# USB-UART-Wiring-Example.net
KiCad netlist of a schematic drawn in EAGLE
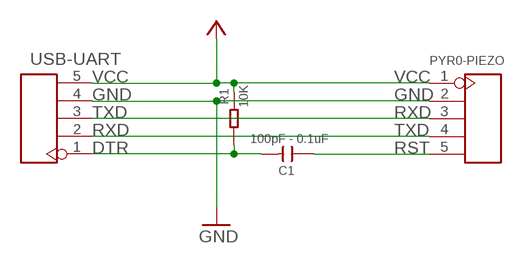
[diagram p0: schematic, sheet 1]

(export (version "E")
  (design (tool "Eeschema 10.0.6"))
  (components
    (comp (ref "C1")
      (value "100pF - 0.1uF")
      (footprint "eagle-import:CAPC1609X80")
      (libsource (lib "eagle-import") (part "SEEED-CAPACITOR_CERAMIC-10UF-25V-10%-X5R(0805)CAP_0603_GEN"))
    )
    (comp (ref "PYR0-PIEZO")
      (value "JST-2.54MM_5P-2.54JST_2.54MM_5P_F")
      (footprint "eagle-import:HDRVR5W64P254_1X5_1270X254X575B")
      (libsource (lib "eagle-import") (part "JST-2.54MM_5P-2.54JST_2.54MM_5P_F"))
    )
    (comp (ref "R1")
      (value "10K")
      (footprint "eagle-import:SEEED-RESISTOR_R0603")
      (libsource (lib "eagle-import") (part "SEEED-RESISTOR_SMD-RES-1.5K-1%-1/10W(0603)DETAILED_MODEL"))
    )
    (comp (ref "USB-UART")
      (value "JST-2.54MM_5P-2.54JST_2.54MM_5P_F")
      (footprint "eagle-import:HDRVR5W64P254_1X5_1270X254X575B")
      (libsource (lib "eagle-import") (part "JST-2.54MM_5P-2.54JST_2.54MM_5P_F"))
    )
  )
  (nets
    (net (code "1") (name "/DTR") (class "Default")
      (node (ref "C1") (pin "2") (pinfunction "2_2") (pintype "passive"))
      (node (ref "R1") (pin "1") (pinfunction "1_1") (pintype "passive"))
      (node (ref "USB-UART") (pin "1") (pinfunction "P$1_1") (pintype "bidirectional"))
    )
    (net (code "2") (name "/RST") (class "Default")
      (node (ref "C1") (pin "1") (pinfunction "1_1") (pintype "passive"))
      (node (ref "PYR0-PIEZO") (pin "5") (pinfunction "P$5_5") (pintype "bidirectional"))
    )
    (net (code "3") (name "/RXD") (class "Default")
      (node (ref "PYR0-PIEZO") (pin "4") (pinfunction "P$4_4") (pintype "bidirectional"))
      (node (ref "USB-UART") (pin "2") (pinfunction "P$2_2") (pintype "bidirectional"))
    )
    (net (code "4") (name "/TXD") (class "Default")
      (node (ref "PYR0-PIEZO") (pin "3") (pinfunction "P$3_3") (pintype "bidirectional"))
      (node (ref "USB-UART") (pin "3") (pinfunction "P$3_3") (pintype "bidirectional"))
    )
    (net (code "5") (name "GND") (class "Default")
      (node (ref "PYR0-PIEZO") (pin "2") (pinfunction "P$2_2") (pintype "bidirectional"))
      (node (ref "USB-UART") (pin "4") (pinfunction "P$4_4") (pintype "bidirectional"))
    )
    (net (code "6") (name "SUPPLY1_VCC") (class "Default")
      (node (ref "PYR0-PIEZO") (pin "1") (pinfunction "P$1_1") (pintype "bidirectional"))
      (node (ref "R1") (pin "2") (pinfunction "2_2") (pintype "passive"))
      (node (ref "USB-UART") (pin "5") (pinfunction "P$5_5") (pintype "bidirectional"))
    )
  )
)
